# SCH_USB_TO_TTL_CONVERTOR.net
KiCad netlist of a schematic drawn in EasyEDA
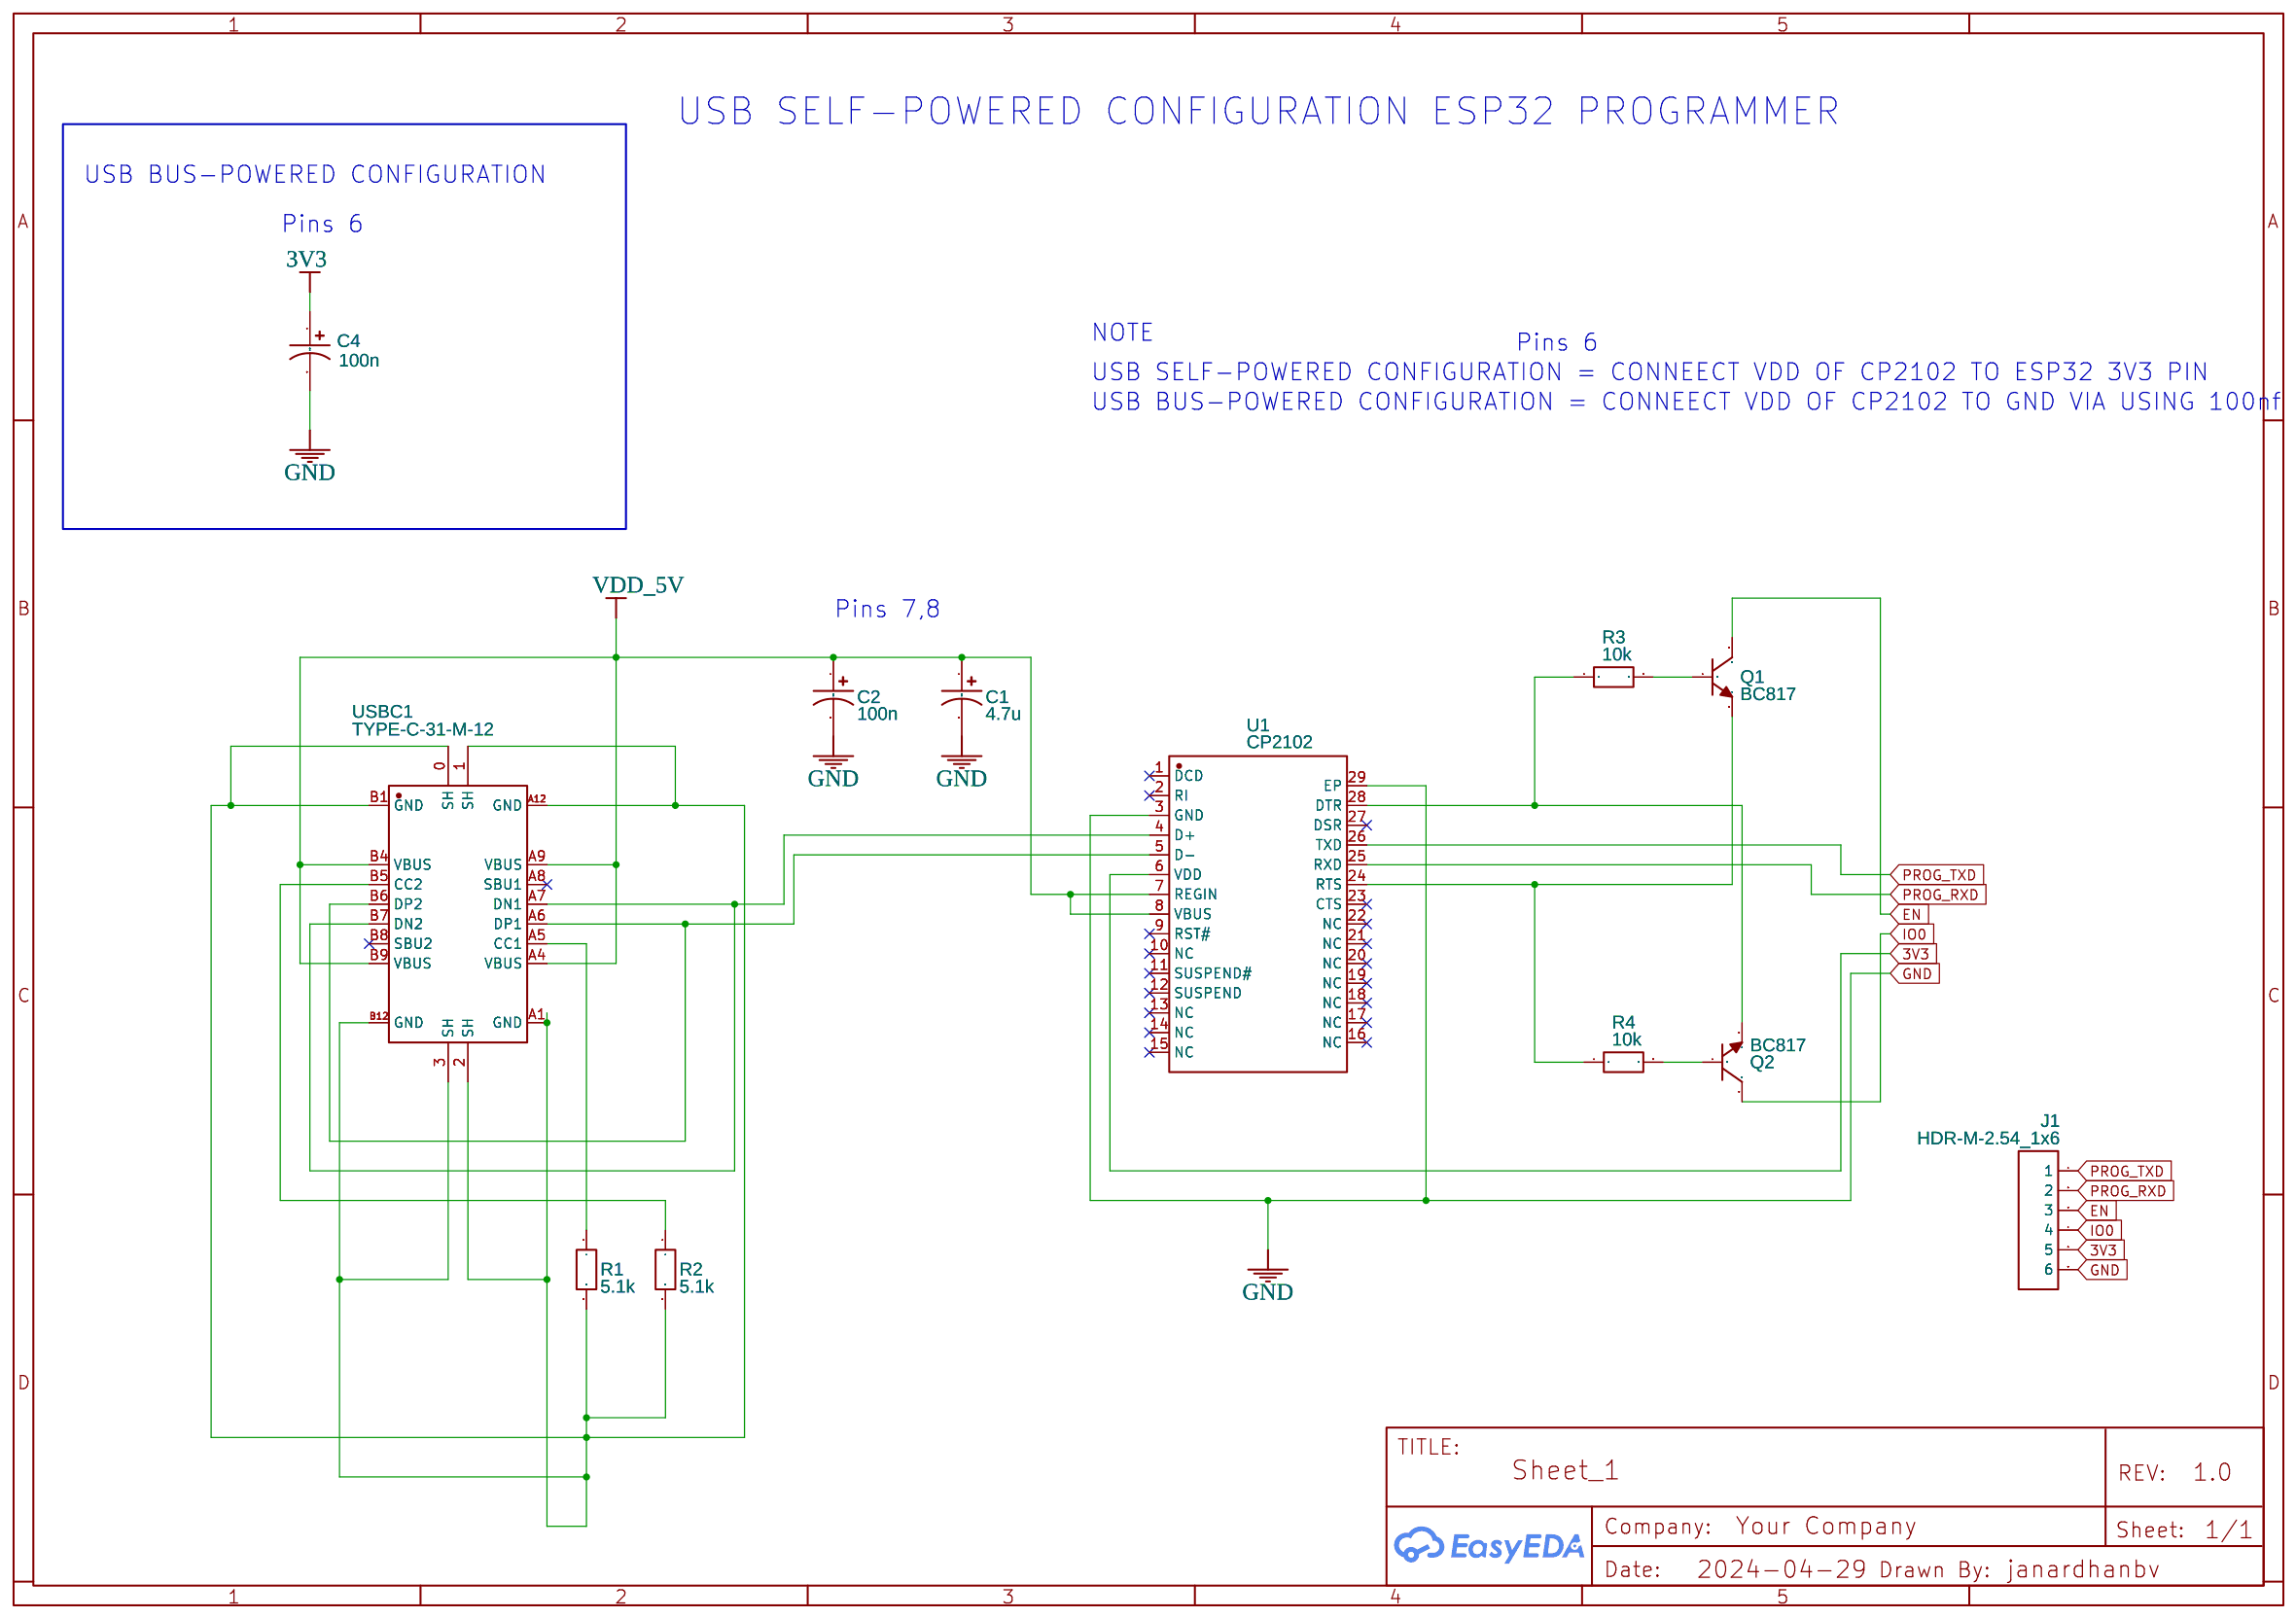
[diagram p0: schematic sheet]

(export (version "E")
  (design (tool "Eeschema 10.0.6"))
  (components
    (comp (ref "C1") (value "4.7u") (libsource (lib "") (part "C_Tan_SMD_A_US")))
    (comp (ref "C2") (value "100n") (libsource (lib "") (part "C_Tan_SMD_A_US")))
    (comp (ref "C4") (value "100n") (libsource (lib "") (part "C_Tan_SMD_A_US_1")))
    (comp (ref "J1") (value "HDR-M-2.54_1x6") (libsource (lib "") (part "HDR-M-2.54_1x6")))
    (comp (ref "Q1")
      (value "BC817")
      (fields (field (name "Manufacturer Part") "BC817-40") (field (name "Manufacturer") "CJ(江苏长电/长晶)"))
      (libsource (lib "") (part "BC817_1"))
    )
    (comp (ref "Q2")
      (value "BC817")
      (fields (field (name "Manufacturer Part") "BC817-40") (field (name "Manufacturer") "CJ(江苏长电/长晶)"))
      (libsource (lib "") (part "BC817"))
    )
    (comp (ref "R1") (value "5.1k") (libsource (lib "") (part "R_0603_EU")))
    (comp (ref "R2") (value "5.1k") (libsource (lib "") (part "R_0603_EU")))
    (comp (ref "R3") (value "10k") (libsource (lib "") (part "R_0603_EU_1")))
    (comp (ref "R4") (value "10k") (libsource (lib "") (part "R_0603_EU_1")))
    (comp (ref "U1") (value "CP2102") (libsource (lib "") (part "CP2102")))
    (comp (ref "USBC1")
      (value "TYPE-C-31-M-12")
      (fields (field (name "Manufacturer") "韩国韩荣"))
      (libsource (lib "") (part "TYPE-C-31-M-12"))
    )
  )
  (nets
    (net (code "1") (name "3V3") (class "Default")
      (node (ref "C4") (pin "1") (pinfunction "1_1") (pintype "unspecified"))
      (node (ref "J1") (pin "5") (pinfunction "5_5") (pintype "input"))
      (node (ref "U1") (pin "6") (pinfunction "VDD_6") (pintype "unspecified"))
    )
    (net (code "2") (name "EN") (class "Default")
      (node (ref "J1") (pin "3") (pinfunction "3_3") (pintype "input"))
      (node (ref "Q1") (pin "3") (pinfunction "C_3") (pintype "unspecified"))
    )
    (net (code "3") (name "GND") (class "Default")
      (node (ref "C1") (pin "2") (pinfunction "2_2") (pintype "unspecified"))
      (node (ref "C2") (pin "2") (pinfunction "2_2") (pintype "unspecified"))
      (node (ref "C4") (pin "2") (pinfunction "2_2") (pintype "unspecified"))
      (node (ref "J1") (pin "6") (pinfunction "6_6") (pintype "input"))
      (node (ref "U1") (pin "29") (pinfunction "EP_29") (pintype "unspecified"))
      (node (ref "U1") (pin "3") (pinfunction "GND_3") (pintype "unspecified"))
    )
    (net (code "4") (name "IO0") (class "Default")
      (node (ref "J1") (pin "4") (pinfunction "4_4") (pintype "input"))
      (node (ref "Q2") (pin "3") (pinfunction "C_3") (pintype "unspecified"))
    )
    (net (code "5") (name "Net-(Q1-B)") (class "Default")
      (node (ref "Q1") (pin "1") (pinfunction "B_1") (pintype "unspecified"))
      (node (ref "R3") (pin "2") (pinfunction "2_2") (pintype "unspecified"))
    )
    (net (code "6") (name "Net-(Q1-E)") (class "Default")
      (node (ref "Q1") (pin "2") (pinfunction "E_2") (pintype "unspecified"))
      (node (ref "R4") (pin "1") (pinfunction "1_1") (pintype "unspecified"))
      (node (ref "U1") (pin "24") (pinfunction "RTS_24") (pintype "unspecified"))
    )
    (net (code "7") (name "Net-(Q2-B)") (class "Default")
      (node (ref "Q2") (pin "1") (pinfunction "B_1") (pintype "unspecified"))
      (node (ref "R4") (pin "2") (pinfunction "2_2") (pintype "unspecified"))
    )
    (net (code "8") (name "Net-(Q2-E)") (class "Default")
      (node (ref "Q2") (pin "2") (pinfunction "E_2") (pintype "unspecified"))
      (node (ref "R3") (pin "1") (pinfunction "1_1") (pintype "unspecified"))
      (node (ref "U1") (pin "28") (pinfunction "DTR_28") (pintype "unspecified"))
    )
    (net (code "9") (name "Net-(R1-Pad2)") (class "Default")
      (node (ref "R1") (pin "2") (pinfunction "2_2") (pintype "unspecified"))
      (node (ref "R2") (pin "2") (pinfunction "2_2") (pintype "unspecified"))
      (node (ref "USBC1") (pin "0") (pinfunction "SH_0") (pintype "unspecified"))
      (node (ref "USBC1") (pin "1") (pinfunction "SH_1") (pintype "unspecified"))
      (node (ref "USBC1") (pin "2") (pinfunction "SH_2") (pintype "unspecified"))
      (node (ref "USBC1") (pin "3") (pinfunction "SH_3") (pintype "unspecified"))
      (node (ref "USBC1") (pin "A1") (pinfunction "GND_A1") (pintype "unspecified"))
      (node (ref "USBC1") (pin "A12") (pinfunction "GND_A12") (pintype "unspecified"))
      (node (ref "USBC1") (pin "B1") (pinfunction "GND_B1") (pintype "unspecified"))
      (node (ref "USBC1") (pin "B12") (pinfunction "GND_B12") (pintype "unspecified"))
    )
    (net (code "10") (name "Net-(U1-D+)") (class "Default")
      (node (ref "U1") (pin "4") (pinfunction "D+_4") (pintype "unspecified"))
      (node (ref "USBC1") (pin "A7") (pinfunction "DN1_A7") (pintype "unspecified"))
      (node (ref "USBC1") (pin "B7") (pinfunction "DN2_B7") (pintype "unspecified"))
    )
    (net (code "11") (name "Net-(U1-D-)") (class "Default")
      (node (ref "U1") (pin "5") (pinfunction "D-_5") (pintype "unspecified"))
      (node (ref "USBC1") (pin "A6") (pinfunction "DP1_A6") (pintype "unspecified"))
      (node (ref "USBC1") (pin "B6") (pinfunction "DP2_B6") (pintype "unspecified"))
    )
    (net (code "12") (name "Net-(USBC1-CC1)") (class "Default")
      (node (ref "R1") (pin "1") (pinfunction "1_1") (pintype "unspecified"))
      (node (ref "USBC1") (pin "A5") (pinfunction "CC1_A5") (pintype "unspecified"))
    )
    (net (code "13") (name "Net-(USBC1-CC2)") (class "Default")
      (node (ref "R2") (pin "1") (pinfunction "1_1") (pintype "unspecified"))
      (node (ref "USBC1") (pin "B5") (pinfunction "CC2_B5") (pintype "unspecified"))
    )
    (net (code "14") (name "PROG_RXD") (class "Default")
      (node (ref "J1") (pin "2") (pinfunction "2_2") (pintype "input"))
      (node (ref "U1") (pin "25") (pinfunction "RXD_25") (pintype "unspecified"))
    )
    (net (code "15") (name "PROG_TXD") (class "Default")
      (node (ref "J1") (pin "1") (pinfunction "1_1") (pintype "input"))
      (node (ref "U1") (pin "26") (pinfunction "TXD_26") (pintype "unspecified"))
    )
    (net (code "16") (name "VDD_5V") (class "Default")
      (node (ref "C1") (pin "1") (pinfunction "1_1") (pintype "unspecified"))
      (node (ref "C2") (pin "1") (pinfunction "1_1") (pintype "unspecified"))
      (node (ref "U1") (pin "7") (pinfunction "REGIN_7") (pintype "unspecified"))
      (node (ref "U1") (pin "8") (pinfunction "VBUS_8") (pintype "unspecified"))
      (node (ref "USBC1") (pin "A4") (pinfunction "VBUS_A4") (pintype "unspecified"))
      (node (ref "USBC1") (pin "A9") (pinfunction "VBUS_A9") (pintype "unspecified"))
      (node (ref "USBC1") (pin "B4") (pinfunction "VBUS_B4") (pintype "unspecified"))
      (node (ref "USBC1") (pin "B9") (pinfunction "VBUS_B9") (pintype "unspecified"))
    )
    (net (code "17") (name "unconnected-(U1-CTS-Pad23)") (class "Default")
      (node (ref "U1") (pin "23") (pinfunction "CTS_23") (pintype "unspecified+no_connect"))
    )
    (net (code "18") (name "unconnected-(U1-DCD-Pad1)") (class "Default")
      (node (ref "U1") (pin "1") (pinfunction "DCD_1") (pintype "unspecified+no_connect"))
    )
    (net (code "19") (name "unconnected-(U1-DSR-Pad27)") (class "Default")
      (node (ref "U1") (pin "27") (pinfunction "DSR_27") (pintype "unspecified+no_connect"))
    )
    (net (code "20") (name "unconnected-(U1-NC-Pad10)") (class "Default")
      (node (ref "U1") (pin "10") (pinfunction "NC_10") (pintype "unspecified+no_connect"))
    )
    (net (code "21") (name "unconnected-(U1-NC-Pad13)") (class "Default")
      (node (ref "U1") (pin "13") (pinfunction "NC_13") (pintype "unspecified+no_connect"))
    )
    (net (code "22") (name "unconnected-(U1-NC-Pad14)") (class "Default")
      (node (ref "U1") (pin "14") (pinfunction "NC_14") (pintype "unspecified+no_connect"))
    )
    (net (code "23") (name "unconnected-(U1-NC-Pad15)") (class "Default")
      (node (ref "U1") (pin "15") (pinfunction "NC_15") (pintype "unspecified+no_connect"))
    )
    (net (code "24") (name "unconnected-(U1-NC-Pad16)") (class "Default")
      (node (ref "U1") (pin "16") (pinfunction "NC_16") (pintype "unspecified+no_connect"))
    )
    (net (code "25") (name "unconnected-(U1-NC-Pad17)") (class "Default")
      (node (ref "U1") (pin "17") (pinfunction "NC_17") (pintype "unspecified+no_connect"))
    )
    (net (code "26") (name "unconnected-(U1-NC-Pad18)") (class "Default")
      (node (ref "U1") (pin "18") (pinfunction "NC_18") (pintype "unspecified+no_connect"))
    )
    (net (code "27") (name "unconnected-(U1-NC-Pad19)") (class "Default")
      (node (ref "U1") (pin "19") (pinfunction "NC_19") (pintype "unspecified+no_connect"))
    )
    (net (code "28") (name "unconnected-(U1-NC-Pad20)") (class "Default")
      (node (ref "U1") (pin "20") (pinfunction "NC_20") (pintype "unspecified+no_connect"))
    )
    (net (code "29") (name "unconnected-(U1-NC-Pad21)") (class "Default")
      (node (ref "U1") (pin "21") (pinfunction "NC_21") (pintype "unspecified+no_connect"))
    )
    (net (code "30") (name "unconnected-(U1-NC-Pad22)") (class "Default")
      (node (ref "U1") (pin "22") (pinfunction "NC_22") (pintype "unspecified+no_connect"))
    )
    (net (code "31") (name "unconnected-(U1-RI-Pad2)") (class "Default")
      (node (ref "U1") (pin "2") (pinfunction "RI_2") (pintype "unspecified+no_connect"))
    )
    (net (code "32") (name "unconnected-(U1-RST#-Pad9)") (class "Default")
      (node (ref "U1") (pin "9") (pinfunction "RST#_9") (pintype "unspecified+no_connect"))
    )
    (net (code "33") (name "unconnected-(U1-SUSPEND#-Pad11)") (class "Default")
      (node (ref "U1") (pin "11") (pinfunction "SUSPEND#_11") (pintype "unspecified+no_connect"))
    )
    (net (code "34") (name "unconnected-(U1-SUSPEND-Pad12)") (class "Default")
      (node (ref "U1") (pin "12") (pinfunction "SUSPEND_12") (pintype "unspecified+no_connect"))
    )
    (net (code "35") (name "unconnected-(USBC1-SBU1-PadA8)") (class "Default")
      (node (ref "USBC1") (pin "A8") (pinfunction "SBU1_A8") (pintype "unspecified+no_connect"))
    )
    (net (code "36") (name "unconnected-(USBC1-SBU2-PadB8)") (class "Default")
      (node (ref "USBC1") (pin "B8") (pinfunction "SBU2_B8") (pintype "unspecified+no_connect"))
    )
  )
)
